# JacdacRHTemp_18.net
KiCad netlist of a schematic drawn in Altium Designer
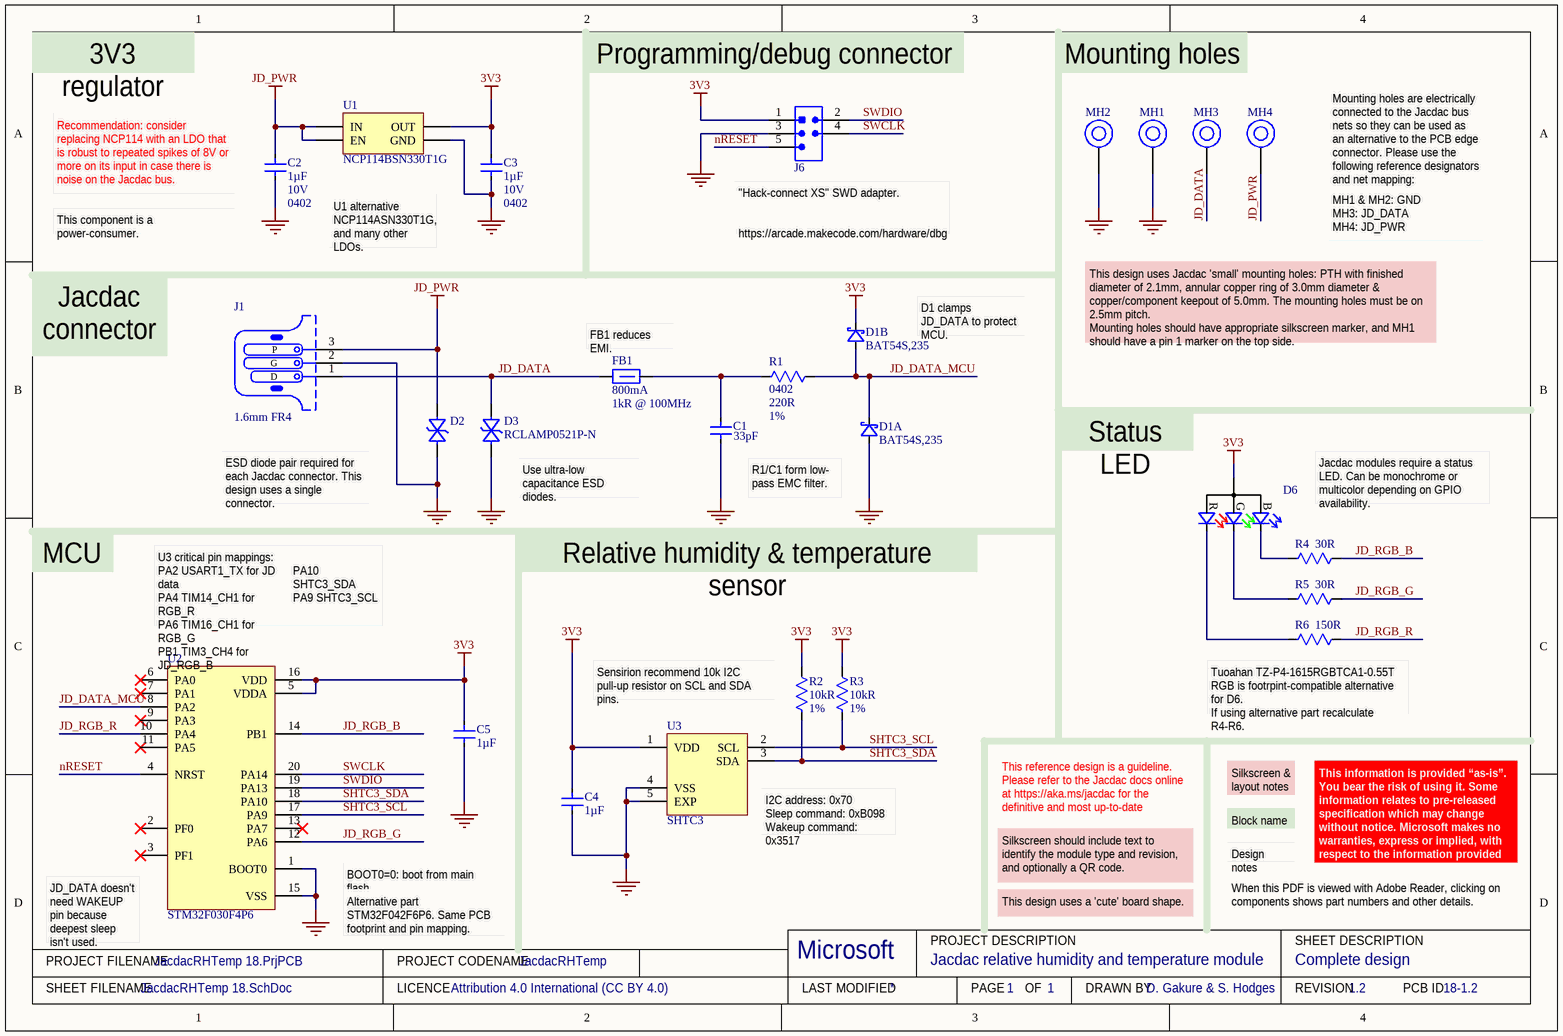
[diagram p0: JacdacRHTemp 18.SchDoc]

(export (version "E")
  (design (tool "Eeschema 10.0.6"))
  (components
    (comp (ref "C1")
      (value "CL05C330JB5NNNC")
      (footprint "C0402_0.55MM - without outline")
      (description "CAP CER 33PF 50V C0G/NP0 0402")
      (fields
        (field (name "MANUFACTURER") "Samsung")
        (field (name "TOLERANCE") "5%")
        (field (name "CAPACITANCE") "33pF")
      )
      (libsource (lib "Samsung") (part "CL05C330JB5NNNC"))
    )
    (comp (ref "C2")
      (value "CL05A105KP5NNNC")
      (footprint "C0402_0.55MM - without outline")
      (description "CAP CER 1UF 10V X5R 0402")
      (fields
        (field (name "MANUFACTURER") "Samsung")
        (field (name "TOLERANCE") "10%")
        (field (name "CAPACITANCE") "1µF")
        (field (name "VOLTAGE RATING") "10V")
        (field (name "CASE CODE (IMPERIAL)") "0402")
        (field (name "CREATED") "DG")
        (field (name "CHECKED") "?")
      )
      (libsource (lib "Samsung") (part "CL05A105KP5NNNC"))
    )
    (comp (ref "C3")
      (value "CL05A105KP5NNNC")
      (footprint "C0402_0.55MM - without outline")
      (description "CAP CER 1UF 10V X5R 0402")
      (fields
        (field (name "MANUFACTURER") "Samsung")
        (field (name "TOLERANCE") "10%")
        (field (name "CAPACITANCE") "1µF")
        (field (name "VOLTAGE RATING") "10V")
        (field (name "CASE CODE (IMPERIAL)") "0402")
        (field (name "CREATED") "DG")
        (field (name "CHECKED") "?")
      )
      (libsource (lib "Samsung") (part "CL05A105KP5NNNC"))
    )
    (comp (ref "C4")
      (value "CL05A105KP5NNNC")
      (footprint "C0402_0.55MM - without outline")
      (description "CAP CER 1UF 10V X5R 0402")
      (fields
        (field (name "MANUFACTURER") "Samsung")
        (field (name "TOLERANCE") "10%")
        (field (name "CAPACITANCE") "1µF")
        (field (name "CREATED") "DG")
        (field (name "CHECKED") "?")
      )
      (libsource (lib "Samsung") (part "CL05A105KP5NNNC"))
    )
    (comp (ref "C5")
      (value "CL05A105KP5NNNC")
      (footprint "C0402_0.55MM - without outline")
      (description "CAP CER 1UF 10V X5R 0402")
      (fields
        (field (name "MANUFACTURER") "Samsung")
        (field (name "TOLERANCE") "10%")
        (field (name "CAPACITANCE") "1µF")
        (field (name "CREATED") "DG")
        (field (name "CHECKED") "?")
      )
      (libsource (lib "Samsung") (part "CL05A105KP5NNNC"))
    )
    (comp (ref "D1")
      (value "BAT54S")
      (footprint "NXP-BAT54S-TO-236AB - without outline")
      (description "DIODE ARRAY SCHOTTKY 30V SOT23")
      (fields (field (name "MANUFACTURER") "Nexperia") (field (name "MANUFACTURER PART NUMBER") "BAT54S,235"))
      (libsource (lib "NXP") (part "BAT54S"))
    )
    (comp (ref "D2")
      (value "RCLAMP0521P-N")
      (footprint "TVS 0402 - L")
      (description "Bidirectional 5V (Max) 6V 16V 3.5A (8/20us) 0402 TVS RoHS")
      (fields
        (field (name "MANUFACTURER") "Born Semiconductor")
        (field (name "CREATED BY") "D Gakure")
        (field (name "CHECKED BY") "?")
      )
      (libsource (lib "BornSemiconductor") (part "RCLAMP0521P-N"))
    )
    (comp (ref "D3")
      (value "RCLAMP0521P-N")
      (footprint "TVS 0402 - L")
      (description "Bidirectional 5V (Max) 6V 16V 3.5A (8/20us) 0402 TVS RoHS")
      (fields
        (field (name "MANUFACTURER") "Born Semiconductor")
        (field (name "MANUFACTURER PART NUMBER") "RCLAMP0521P-N")
        (field (name "CREATED BY") "D Gakure")
        (field (name "CHECKED BY") "?")
      )
      (libsource (lib "BornSemiconductor") (part "RCLAMP0521P-N"))
    )
    (comp (ref "D6")
      (value "TZ-P4-1615RGBTCA1-0.55T")
      (footprint "TZ-P4-1615RGBTCA1-0.55T")
      (description "1615 Light Emitting Diodes (LED) RoHS")
      (fields
        (field (name "MANUFACTURER") "TUOZHAN")
        (field (name "CREATED BY") "D. Gakure")
        (field (name "CHECKED BY") "?")
      )
      (libsource (lib "Tuozhan") (part "TZ-P4-1615RGBTCA1-0.55T"))
    )
    (comp (ref "FB1")
      (value "TDK MPZ1608S102ATA00")
      (footprint "TDK MPZ1608 0.8mm - without outline")
      (description "0603 1k@100MHz 0.8A chip")
      (fields
        (field (name "TOLERANCE") "25%")
        (field (name "MANUFACTURER") "TDK")
        (field (name "CURRENT RATING") "800mA")
        (field (name "IMPEDANCE") "1kR @ 100MHz")
      )
      (libsource (lib "TDK") (part "TDK MPZ1608S102ATA00"))
    )
    (comp (ref "J1")
      (value "3 pin JACDAC edge connector")
      (footprint "JACDAC_EDGE_CONNECTOR_NO_TRACES")
      (description "3 pin Jacdac edge connector 1.27mm pitch")
      (fields
        (field (name "MANUFACTURER PART NUMBER") "JACDAC_EDGE_CONNECTOR")
        (field (name "PCB TYPE") "1.6mm FR4")
        (field (name "CHECKED BY") "?")
        (field (name "CREATED BY") "D. Gakure")
      )
      (libsource (lib "generic-con") (part "Jacdac edge connector"))
    )
    (comp (ref "J6")
      (value "Hack Connect Mini 1.27 mm pitch 2-row")
      (footprint "HACK_CONNECT_MINI_5_X_1_27")
      (libsource (lib "HackConnect") (part "HACK_CONNECT_MINI"))
    )
    (comp (ref "MH1")
      (value "MH_5.0MMK_3.0MMC_2.1MMD_PTH")
      (footprint "MH_5.0MMK_3.0MMC_2.1MMD_PTH")
      (description "Mounting Hole 5.0mm keepout, 3.0mm annualar ring and 2.1mm Drill PTH")
      (libsource (lib "generic") (part "MH_5.0MMK_3.0MMC_2.1MMD_PTH"))
    )
    (comp (ref "MH2")
      (value "MH_5.0MMK_3.0MMC_2.1MMD_PTH")
      (footprint "MH_5.0MMK_3.0MMC_2.1MMD_PTH")
      (description "Mounting Hole 5.0mm keepout, 3.0mm annualar ring and 2.1mm Drill PTH")
      (libsource (lib "generic") (part "MH_5.0MMK_3.0MMC_2.1MMD_PTH"))
    )
    (comp (ref "MH3")
      (value "MH_5.0MMK_3.0MMC_2.1MMD_PTH")
      (footprint "MH_5.0MMK_3.0MMC_2.1MMD_PTH")
      (description "Mounting Hole 5.0mm keepout, 3.0mm annualar ring and 2.1mm Drill PTH")
      (libsource (lib "generic") (part "MH_5.0MMK_3.0MMC_2.1MMD_PTH"))
    )
    (comp (ref "MH4")
      (value "MH_5.0MMK_3.0MMC_2.1MMD_PTH")
      (footprint "MH_5.0MMK_3.0MMC_2.1MMD_PTH")
      (description "Mounting Hole 5.0mm keepout, 3.0mm annualar ring and 2.1mm Drill PTH")
      (libsource (lib "generic") (part "MH_5.0MMK_3.0MMC_2.1MMD_PTH"))
    )
    (comp (ref "R1")
      (value "RC0402FR-07220RL")
      (footprint "R0402 - Without outline")
      (description "RES SMD 220 OHM 1% 1/16W 0402")
      (fields
        (field (name "MANUFACTURER") "Yageo")
        (field (name "CASE CODE (IMPERIAL)") "0402")
        (field (name "RESISTANCE") "220R")
        (field (name "TOLERANCE") "1%")
        (field (name "CREATED") "D.G")
        (field (name "CHECKED") "?")
      )
      (libsource (lib "Yageo") (part "RC0402FR-07220RL"))
    )
    (comp (ref "R2")
      (value "10k")
      (footprint "R0402 - Without outline")
      (description "RES SMD 10K OHM 1% 1/16W 0402")
      (fields
        (field (name "MANUFACTURER") "Yageo")
        (field (name "MANUFACTURER PART NUMBER") "RC0402FR-0710KL")
        (field (name "RESISTANCE") "10kR")
        (field (name "TOLERANCE") "1%")
        (field (name "CHECKED") "?")
        (field (name "CREATED") "DG")
      )
      (libsource (lib "Yageo") (part "RC0402FR-0710KL"))
    )
    (comp (ref "R3")
      (value "10k")
      (footprint "R0402 - Without outline")
      (description "RES SMD 10K OHM 1% 1/16W 0402")
      (fields
        (field (name "MANUFACTURER") "Yageo")
        (field (name "MANUFACTURER PART NUMBER") "RC0402FR-0710KL")
        (field (name "RESISTANCE") "10kR")
        (field (name "TOLERANCE") "1%")
        (field (name "CHECKED") "?")
        (field (name "CREATED") "DG")
      )
      (libsource (lib "Yageo") (part "RC0402FR-0710KL"))
    )
    (comp (ref "R4")
      (value "RC0402FR-0730RL")
      (footprint "R0402 - Without outline")
      (description "RES SMD 30 OHM 1% 1/16W 0402")
      (fields
        (field (name "MANUFACTURER") "Yageo")
        (field (name "RESISTANCE") "30R")
        (field (name "TOLERANCE") "1%")
        (field (name "CREATED BY") "D. Gakure")
        (field (name "CHECKED BY") "?")
      )
      (libsource (lib "Yageo") (part "RC0402FR-0730RL"))
    )
    (comp (ref "R5")
      (value "RC0402FR-0730RL")
      (footprint "R0402 - Without outline")
      (description "RES SMD 30 OHM 1% 1/16W 0402")
      (fields
        (field (name "MANUFACTURER") "Yageo")
        (field (name "RESISTANCE") "30R")
        (field (name "TOLERANCE") "1%")
        (field (name "CREATED BY") "D. Gakure")
        (field (name "CHECKED BY") "?")
      )
      (libsource (lib "Yageo") (part "RC0402FR-0730RL"))
    )
    (comp (ref "R6")
      (value "RC0402FR-07150RL")
      (footprint "R0402 - Without outline")
      (description "RES SMD 150 OHM 1% 1/16W 0402")
      (fields
        (field (name "MANUFACTURER") "Yageo")
        (field (name "RESISTANCE") "150R")
        (field (name "TOLERANCE") "1%")
        (field (name "CREATED BY") "D. Gakure")
        (field (name "CHECKED BY") "?")
      )
      (libsource (lib "Yageo") (part "RC0402FR-07150RL"))
    )
    (comp (ref "U1")
      (value "LDO 3.3V/300 mA")
      (footprint "ON_SEMI-SOT23-5 - without outline")
      (description "CMOS Low Dropout Regulator (LDO), 300 mA 3.3V, Non-Active Discharge, TSOP5")
      (fields
        (field (name "MANUFACTURER") "ON Semiconductor")
        (field (name "MANUFACTURER PART NUMBER") "NCP114BSN330T1G")
      )
      (libsource (lib "OnSemiconductor") (part "NCP114BSN330T1G"))
    )
    (comp (ref "U2")
      (value "STM32F030F4P6")
      (footprint "20-TSSOP - without outline")
      (description "ARM Cortex-M0 STM32F0 Microcontroller IC 32-Bit 48MHz 16KB (16K x 8) FLASH")
      (fields
        (field (name "MANUFACTURER") "STMicroelectronics")
        (field (name "MANUFACTURER PART NUMBER") "STM32F030F4P6")
        (field (name "CREATED") "DG")
        (field (name "CHECKED") "?")
        (field (name "CREATED BY") "D. Gakure")
        (field (name "CHECKED BY") "?")
      )
      (libsource (lib "ST") (part "ST STM32F030F4P6"))
    )
    (comp (ref "U3")
      (value "SHTC3")
      (footprint "SHTC3_4_WDFN")
      (description "Humidity Temperature Sensor 0 ~ 100% RH I²C ±2% RH 8s Surface Mount")
      (fields
        (field (name "MANUFACTURER") "Sensirion")
        (field (name "MANUFACTURER PART NUMBER") "SHTC3")
        (field (name "CREATED BY") "D. Gakure")
        (field (name "CHECKED BY") "?")
      )
      (libsource (lib "Sensirion") (part "SHTC3"))
    )
  )
  (nets
    (net (code "1") (name "/JD_DATA") (class "Default")
      (node (ref "D3") (pin "1") (pinfunction "K_1") (pintype "passive"))
      (node (ref "FB1") (pin "1") (pinfunction "1_1") (pintype "passive"))
      (node (ref "J1") (pin "1") (pinfunction "D_1") (pintype "passive"))
      (node (ref "MH3") (pin "1") (pinfunction "1_1") (pintype "passive"))
    )
    (net (code "2") (name "/JD_DATA_MCU") (class "Default")
      (node (ref "D1") (pin "3") (pinfunction "K_3") (pintype "passive"))
      (node (ref "R1") (pin "1") (pinfunction "1_1") (pintype "passive"))
      (node (ref "U2") (pin "8") (pinfunction "PA2_8") (pintype "passive"))
    )
    (net (code "3") (name "/JD_RGB_B") (class "Default")
      (node (ref "R4") (pin "2") (pinfunction "2_2") (pintype "passive"))
      (node (ref "U2") (pin "14") (pinfunction "PB1_14") (pintype "passive"))
    )
    (net (code "4") (name "/JD_RGB_G") (class "Default")
      (node (ref "R5") (pin "2") (pinfunction "2_2") (pintype "passive"))
      (node (ref "U2") (pin "12") (pinfunction "PA6_12") (pintype "passive"))
    )
    (net (code "5") (name "/JD_RGB_R") (class "Default")
      (node (ref "R6") (pin "2") (pinfunction "2_2") (pintype "passive"))
      (node (ref "U2") (pin "10") (pinfunction "PA4_10") (pintype "passive"))
    )
    (net (code "6") (name "/SHTC3_SCL") (class "Default")
      (node (ref "R3") (pin "2") (pinfunction "2_2") (pintype "passive"))
      (node (ref "U2") (pin "17") (pinfunction "PA9_17") (pintype "passive"))
      (node (ref "U3") (pin "2") (pinfunction "SCL_2") (pintype "passive"))
    )
    (net (code "7") (name "/SHTC3_SDA") (class "Default")
      (node (ref "R2") (pin "2") (pinfunction "2_2") (pintype "passive"))
      (node (ref "U2") (pin "18") (pinfunction "PA10_18") (pintype "passive"))
      (node (ref "U3") (pin "3") (pinfunction "SDA_3") (pintype "passive"))
    )
    (net (code "8") (name "/SWCLK") (class "Default")
      (node (ref "J6") (pin "4") (pinfunction "SWCLK_4") (pintype "passive"))
      (node (ref "U2") (pin "20") (pinfunction "PA14_20") (pintype "passive"))
    )
    (net (code "9") (name "/SWDIO") (class "Default")
      (node (ref "J6") (pin "2") (pinfunction "SWDIO_2") (pintype "passive"))
      (node (ref "U2") (pin "19") (pinfunction "PA13_19") (pintype "passive"))
    )
    (net (code "10") (name "/nRESET") (class "Default")
      (node (ref "J6") (pin "5") (pinfunction "RESET_5") (pintype "passive"))
      (node (ref "U2") (pin "4") (pinfunction "NRST_4") (pintype "passive"))
    )
    (net (code "11") (name "3V3") (class "Default")
      (node (ref "C3") (pin "2") (pinfunction "2_2") (pintype "passive"))
      (node (ref "C4") (pin "2") (pinfunction "2_2") (pintype "passive"))
      (node (ref "C5") (pin "2") (pinfunction "2_2") (pintype "passive"))
      (node (ref "D1") (pin "2") (pinfunction "K_2") (pintype "passive"))
      (node (ref "D6") (pin "1") (pinfunction "A_1") (pintype "passive"))
      (node (ref "J6") (pin "1") (pinfunction "VCC_1") (pintype "passive"))
      (node (ref "R2") (pin "1") (pinfunction "1_1") (pintype "passive"))
      (node (ref "R3") (pin "1") (pinfunction "1_1") (pintype "passive"))
      (node (ref "U1") (pin "5") (pinfunction "OUT_5") (pintype "passive"))
      (node (ref "U2") (pin "16") (pinfunction "VDD_16") (pintype "power_in"))
      (node (ref "U2") (pin "5") (pinfunction "VDDA_5") (pintype "power_in"))
      (node (ref "U3") (pin "1") (pinfunction "VDD_1") (pintype "passive"))
    )
    (net (code "12") (name "GND") (class "Default")
      (node (ref "C1") (pin "1") (pinfunction "1_1") (pintype "passive"))
      (node (ref "C2") (pin "1") (pinfunction "1_1") (pintype "passive"))
      (node (ref "C3") (pin "1") (pinfunction "1_1") (pintype "passive"))
      (node (ref "C4") (pin "1") (pinfunction "1_1") (pintype "passive"))
      (node (ref "C5") (pin "1") (pinfunction "1_1") (pintype "passive"))
      (node (ref "D1") (pin "1") (pinfunction "A_1") (pintype "passive"))
      (node (ref "D2") (pin "2") (pinfunction "A_2") (pintype "passive"))
      (node (ref "D3") (pin "2") (pinfunction "A_2") (pintype "passive"))
      (node (ref "J1") (pin "2") (pinfunction "G_2") (pintype "passive"))
      (node (ref "J6") (pin "3") (pinfunction "GND_3") (pintype "passive"))
      (node (ref "MH1") (pin "1") (pinfunction "1_1") (pintype "passive"))
      (node (ref "MH2") (pin "1") (pinfunction "1_1") (pintype "passive"))
      (node (ref "U1") (pin "2") (pinfunction "GND_2") (pintype "passive"))
      (node (ref "U2") (pin "1") (pinfunction "BOOT0_1") (pintype "passive"))
      (node (ref "U2") (pin "15") (pinfunction "VSS_15") (pintype "power_in"))
      (node (ref "U3") (pin "4") (pinfunction "VSS_4") (pintype "passive"))
      (node (ref "U3") (pin "5") (pinfunction "EXP_5") (pintype "passive"))
    )
    (net (code "13") (name "JD_PWR") (class "Default")
      (node (ref "C2") (pin "2") (pinfunction "2_2") (pintype "passive"))
      (node (ref "D2") (pin "1") (pinfunction "K_1") (pintype "passive"))
      (node (ref "J1") (pin "3") (pinfunction "P_3") (pintype "passive"))
      (node (ref "MH4") (pin "1") (pinfunction "1_1") (pintype "passive"))
      (node (ref "U1") (pin "1") (pinfunction "IN_1") (pintype "passive"))
      (node (ref "U1") (pin "3") (pinfunction "EN_3") (pintype "passive"))
    )
    (net (code "14") (name "Net-(C1-Pad2)") (class "Default")
      (node (ref "C1") (pin "2") (pinfunction "2_2") (pintype "passive"))
      (node (ref "FB1") (pin "2") (pinfunction "2_2") (pintype "passive"))
      (node (ref "R1") (pin "2") (pinfunction "2_2") (pintype "passive"))
    )
    (net (code "15") (name "Net-(D6-B)") (class "Default")
      (node (ref "D6") (pin "4") (pinfunction "B_4") (pintype "passive"))
      (node (ref "R4") (pin "1") (pinfunction "1_1") (pintype "passive"))
    )
    (net (code "16") (name "Net-(D6-G)") (class "Default")
      (node (ref "D6") (pin "3") (pinfunction "G_3") (pintype "passive"))
      (node (ref "R5") (pin "1") (pinfunction "1_1") (pintype "passive"))
    )
    (net (code "17") (name "Net-(D6-R)") (class "Default")
      (node (ref "D6") (pin "2") (pinfunction "R_2") (pintype "passive"))
      (node (ref "R6") (pin "1") (pinfunction "1_1") (pintype "passive"))
    )
    (net (code "18") (name "unconnected-(U2-PA0-Pad6)") (class "Default")
      (node (ref "U2") (pin "6") (pinfunction "PA0_6") (pintype "passive+no_connect"))
    )
    (net (code "19") (name "unconnected-(U2-PA1-Pad7)") (class "Default")
      (node (ref "U2") (pin "7") (pinfunction "PA1_7") (pintype "passive+no_connect"))
    )
    (net (code "20") (name "unconnected-(U2-PA3-Pad9)") (class "Default")
      (node (ref "U2") (pin "9") (pinfunction "PA3_9") (pintype "passive+no_connect"))
    )
    (net (code "21") (name "unconnected-(U2-PA5-Pad11)") (class "Default")
      (node (ref "U2") (pin "11") (pinfunction "PA5_11") (pintype "passive+no_connect"))
    )
    (net (code "22") (name "unconnected-(U2-PA7-Pad13)") (class "Default")
      (node (ref "U2") (pin "13") (pinfunction "PA7_13") (pintype "passive+no_connect"))
    )
    (net (code "23") (name "unconnected-(U2-PF0-Pad2)") (class "Default")
      (node (ref "U2") (pin "2") (pinfunction "PF0_2") (pintype "passive+no_connect"))
    )
    (net (code "24") (name "unconnected-(U2-PF1-Pad3)") (class "Default")
      (node (ref "U2") (pin "3") (pinfunction "PF1_3") (pintype "passive+no_connect"))
    )
  )
)
